# reload.net
KiCad netlist of a schematic drawn in EAGLE
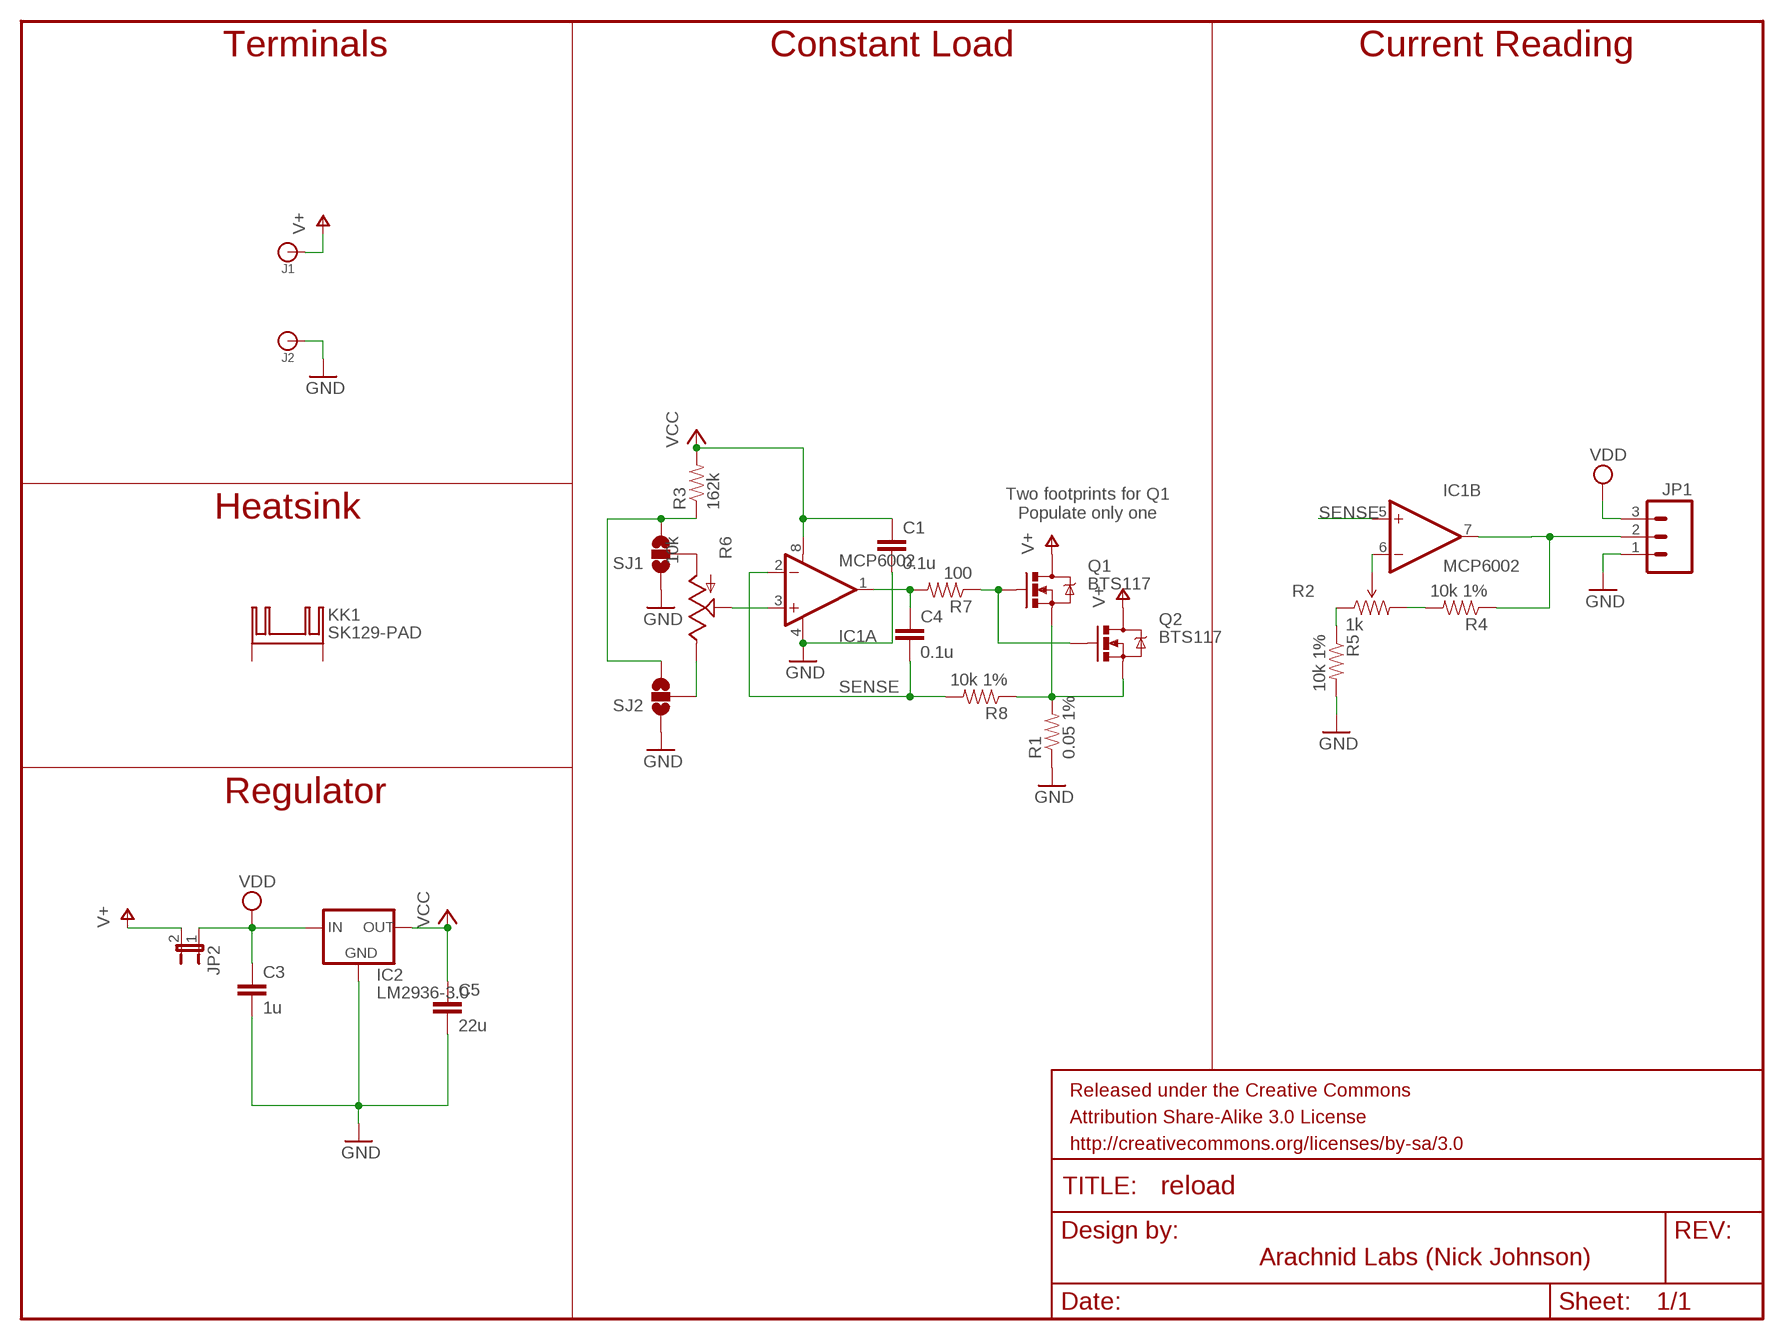
[diagram p0: schematic, sheet 1]

(export (version "E")
  (design (tool "Eeschema 10.0.6"))
  (components
    (comp (ref "C1")
      (value "0.1u")
      (footprint "eagle-import:0805")
      (libsource (lib "eagle-import") (part "CAP0805"))
    )
    (comp (ref "C3")
      (value "1u")
      (footprint "eagle-import:0805")
      (libsource (lib "eagle-import") (part "CAP0805"))
    )
    (comp (ref "C4")
      (value "0.1u")
      (footprint "eagle-import:0805")
      (libsource (lib "eagle-import") (part "CAP0805"))
    )
    (comp (ref "C5")
      (value "22u")
      (footprint "eagle-import:0805")
      (libsource (lib "eagle-import") (part "CAP0805"))
    )
    (comp (ref "IC1")
      (value "MCP6002")
      (footprint "eagle-import:SOP08")
      (libsource (lib "eagle-import") (part "OPAMP-DUALMS"))
    )
    (comp (ref "IC2")
      (value "LM2936-3.0")
      (footprint "eagle-import:SOT223")
      (libsource (lib "eagle-import") (part "V_REG_MIC2920"))
    )
    (comp (ref "J1")
      (value "BANANA_CONN")
      (footprint "eagle-import:BANANA_CONN")
      (libsource (lib "eagle-import") (part "BANANA_CONN"))
    )
    (comp (ref "J2")
      (value "BANANA_CONN")
      (footprint "eagle-import:BANANA_CONN")
      (libsource (lib "eagle-import") (part "BANANA_CONN"))
    )
    (comp (ref "JP1")
      (value "M031X03_NO_SILK")
      (footprint "eagle-import:1X03_NO_SILK")
      (libsource (lib "eagle-import") (part "M031X03_NO_SILK"))
    )
    (comp (ref "JP2")
      (value "JUMPER-2SMD-NC")
      (footprint "eagle-import:SJ_2S")
      (libsource (lib "eagle-import") (part "JUMPER-2SMD-NC"))
    )
    (comp (ref "KK1")
      (value "SK129-PAD")
      (footprint "eagle-import:SK129")
      (libsource (lib "eagle-import") (part "SK129-PAD"))
    )
    (comp (ref "Q1")
      (value "BTS117")
      (footprint "eagle-import:TO220V")
      (libsource (lib "eagle-import") (part "MOSFET-NCHANNELPTH2"))
    )
    (comp (ref "Q2")
      (value "BTS117")
      (footprint "eagle-import:TO220V-NOSILK")
      (libsource (lib "eagle-import") (part "MOSFET-NCHANNELTO220V-NOSILK"))
    )
    (comp (ref "R1")
      (value "0.05 1%")
      (footprint "eagle-import:R2512")
      (libsource (lib "eagle-import") (part "RESISTOR2512"))
    )
    (comp (ref "R2")
      (value "1k")
      (footprint "eagle-import:TRIMPOT-EVN5E")
      (libsource (lib "eagle-import") (part "TRIMPOTEVN5E"))
    )
    (comp (ref "R3")
      (value "162k")
      (footprint "eagle-import:0805")
      (libsource (lib "eagle-import") (part "RESISTOR0805-RES"))
    )
    (comp (ref "R4")
      (value "10k 1%")
      (footprint "eagle-import:0805")
      (libsource (lib "eagle-import") (part "RESISTOR0805-RES"))
    )
    (comp (ref "R5")
      (value "10k 1%")
      (footprint "eagle-import:0805")
      (libsource (lib "eagle-import") (part "RESISTOR0805-RES"))
    )
    (comp (ref "R6")
      (value "10k")
      (footprint "eagle-import:ALPS_POT")
      (libsource (lib "eagle-import") (part "POT"))
    )
    (comp (ref "R7")
      (value "100")
      (footprint "eagle-import:0805")
      (libsource (lib "eagle-import") (part "RESISTOR0805-RES"))
    )
    (comp (ref "R8")
      (value "10k 1%")
      (footprint "eagle-import:0805")
      (libsource (lib "eagle-import") (part "RESISTOR0805-RES"))
    )
    (comp (ref "SJ1")
      (value "SOLDERJUMPER_2WAYPASTE2&3")
      (footprint "eagle-import:SJ_3_PASTE2&3")
      (libsource (lib "eagle-import") (part "SOLDERJUMPER_2WAYPASTE2&3"))
    )
    (comp (ref "SJ2")
      (value "SOLDERJUMPER_2WAYPASTE1&2")
      (footprint "eagle-import:SJ_3_PASTE1&2")
      (libsource (lib "eagle-import") (part "SOLDERJUMPER_2WAYPASTE1&2"))
    )
  )
  (nets
    (net (code "1") (name "/SENSE") (class "Default")
      (node (ref "C4") (pin "2") (pinfunction "2_2") (pintype "passive"))
      (node (ref "IC1") (pin "2") (pinfunction "-IN_2") (pintype "input"))
      (node (ref "IC1") (pin "5") (pinfunction "+IN_5") (pintype "input"))
      (node (ref "R8") (pin "2") (pinfunction "2_2") (pintype "passive"))
    )
    (net (code "2") (name "GND") (class "Default")
      (node (ref "C1") (pin "2") (pinfunction "2_2") (pintype "passive"))
      (node (ref "C3") (pin "2") (pinfunction "2_2") (pintype "passive"))
      (node (ref "C5") (pin "2") (pinfunction "2_2") (pintype "passive"))
      (node (ref "IC1") (pin "4") (pinfunction "V-_4") (pintype "power_in"))
      (node (ref "IC2") (pin "2") (pinfunction "GND_2") (pintype "input"))
      (node (ref "J2") (pin "P$1") (pinfunction "1_P$1") (pintype "passive"))
      (node (ref "JP1") (pin "1") (pinfunction "1_1") (pintype "passive"))
      (node (ref "R1") (pin "1") (pinfunction "1_1") (pintype "passive"))
      (node (ref "R5") (pin "2") (pinfunction "2_2") (pintype "passive"))
      (node (ref "SJ1") (pin "1") (pinfunction "1_1") (pintype "passive"))
      (node (ref "SJ2") (pin "1") (pinfunction "1_1") (pintype "passive"))
    )
    (net (code "3") (name "Net-(IC1A-+IN)") (class "Default")
      (node (ref "IC1") (pin "3") (pinfunction "+IN_3") (pintype "input"))
      (node (ref "R6") (pin "P$2") (pinfunction "S_P$2") (pintype "passive"))
    )
    (net (code "4") (name "Net-(IC1A-OUT)") (class "Default")
      (node (ref "C4") (pin "1") (pinfunction "1_1") (pintype "passive"))
      (node (ref "IC1") (pin "1") (pinfunction "OUT_1") (pintype "output"))
      (node (ref "R7") (pin "2") (pinfunction "2_2") (pintype "passive"))
    )
    (net (code "5") (name "Net-(IC1B--IN)") (class "Default")
      (node (ref "IC1") (pin "6") (pinfunction "-IN_6") (pintype "input"))
      (node (ref "R2") (pin "2") (pinfunction "WIPER_2") (pintype "passive"))
    )
    (net (code "6") (name "Net-(IC1B-OUT)") (class "Default")
      (node (ref "IC1") (pin "7") (pinfunction "OUT_7") (pintype "output"))
      (node (ref "JP1") (pin "2") (pinfunction "2_2") (pintype "passive"))
      (node (ref "R4") (pin "1") (pinfunction "1_1") (pintype "passive"))
    )
    (net (code "7") (name "Net-(Q1-G)") (class "Default")
      (node (ref "Q1") (pin "1") (pinfunction "G_1") (pintype "passive"))
      (node (ref "Q2") (pin "1") (pinfunction "G_1") (pintype "passive"))
      (node (ref "R7") (pin "1") (pinfunction "1_1") (pintype "passive"))
    )
    (net (code "8") (name "Net-(Q1-S)") (class "Default")
      (node (ref "Q1") (pin "3") (pinfunction "S_3") (pintype "passive"))
      (node (ref "Q2") (pin "3") (pinfunction "S_3") (pintype "passive"))
      (node (ref "R1") (pin "2") (pinfunction "2_2") (pintype "passive"))
      (node (ref "R8") (pin "1") (pinfunction "1_1") (pintype "passive"))
    )
    (net (code "9") (name "Net-(R2-CCW)") (class "Default")
      (node (ref "R2") (pin "1") (pinfunction "CCW_1") (pintype "passive"))
      (node (ref "R5") (pin "1") (pinfunction "1_1") (pintype "passive"))
    )
    (net (code "10") (name "Net-(R2-CW)") (class "Default")
      (node (ref "R2") (pin "3") (pinfunction "CW_3") (pintype "passive"))
      (node (ref "R4") (pin "2") (pinfunction "2_2") (pintype "passive"))
    )
    (net (code "11") (name "Net-(R3-Pad1)") (class "Default")
      (node (ref "R3") (pin "1") (pinfunction "1_1") (pintype "passive"))
      (node (ref "SJ1") (pin "3") (pinfunction "3_3") (pintype "passive"))
      (node (ref "SJ2") (pin "3") (pinfunction "3_3") (pintype "passive"))
    )
    (net (code "12") (name "Net-(R6-A)") (class "Default")
      (node (ref "R6") (pin "P$3") (pinfunction "A_P$3") (pintype "passive"))
      (node (ref "SJ1") (pin "2") (pinfunction "2_2") (pintype "passive"))
    )
    (net (code "13") (name "Net-(R6-E)") (class "Default")
      (node (ref "R6") (pin "P$1") (pinfunction "E_P$1") (pintype "passive"))
      (node (ref "SJ2") (pin "2") (pinfunction "2_2") (pintype "passive"))
    )
    (net (code "14") (name "V+") (class "Default")
      (node (ref "J1") (pin "P$1") (pinfunction "1_P$1") (pintype "passive"))
      (node (ref "JP2") (pin "2") (pinfunction "2_2") (pintype "passive"))
      (node (ref "Q1") (pin "2") (pinfunction "D_2") (pintype "passive"))
      (node (ref "Q2") (pin "2") (pinfunction "D_2") (pintype "passive"))
    )
    (net (code "15") (name "VCC") (class "Default")
      (node (ref "C1") (pin "1") (pinfunction "1_1") (pintype "passive"))
      (node (ref "C5") (pin "1") (pinfunction "1_1") (pintype "passive"))
      (node (ref "IC1") (pin "8") (pinfunction "V+_8") (pintype "power_in"))
      (node (ref "IC2") (pin "3") (pinfunction "OUT_3") (pintype "output"))
      (node (ref "R3") (pin "2") (pinfunction "2_2") (pintype "passive"))
    )
    (net (code "16") (name "VDD") (class "Default")
      (node (ref "C3") (pin "1") (pinfunction "1_1") (pintype "passive"))
      (node (ref "IC2") (pin "1") (pinfunction "IN_1") (pintype "input"))
      (node (ref "JP1") (pin "3") (pinfunction "3_3") (pintype "passive"))
      (node (ref "JP2") (pin "1") (pinfunction "1_1") (pintype "passive"))
    )
    (net (code "17") (name "unconnected-(KK1-K-PadA2,5)") (class "Default")
      (node (ref "KK1") (pin "A2,5") (pinfunction "K_A2,5") (pintype "passive"))
    )
    (net (code "18") (name "unconnected-(KK1-K-PadB2,5)") (class "Default")
      (node (ref "KK1") (pin "B2,5") (pinfunction "K_B2,5") (pintype "passive"))
    )
  )
)
